# c12880ma-spectrometer-3_3v-breakout-mk-1.net
KiCad netlist of a schematic drawn in EAGLE
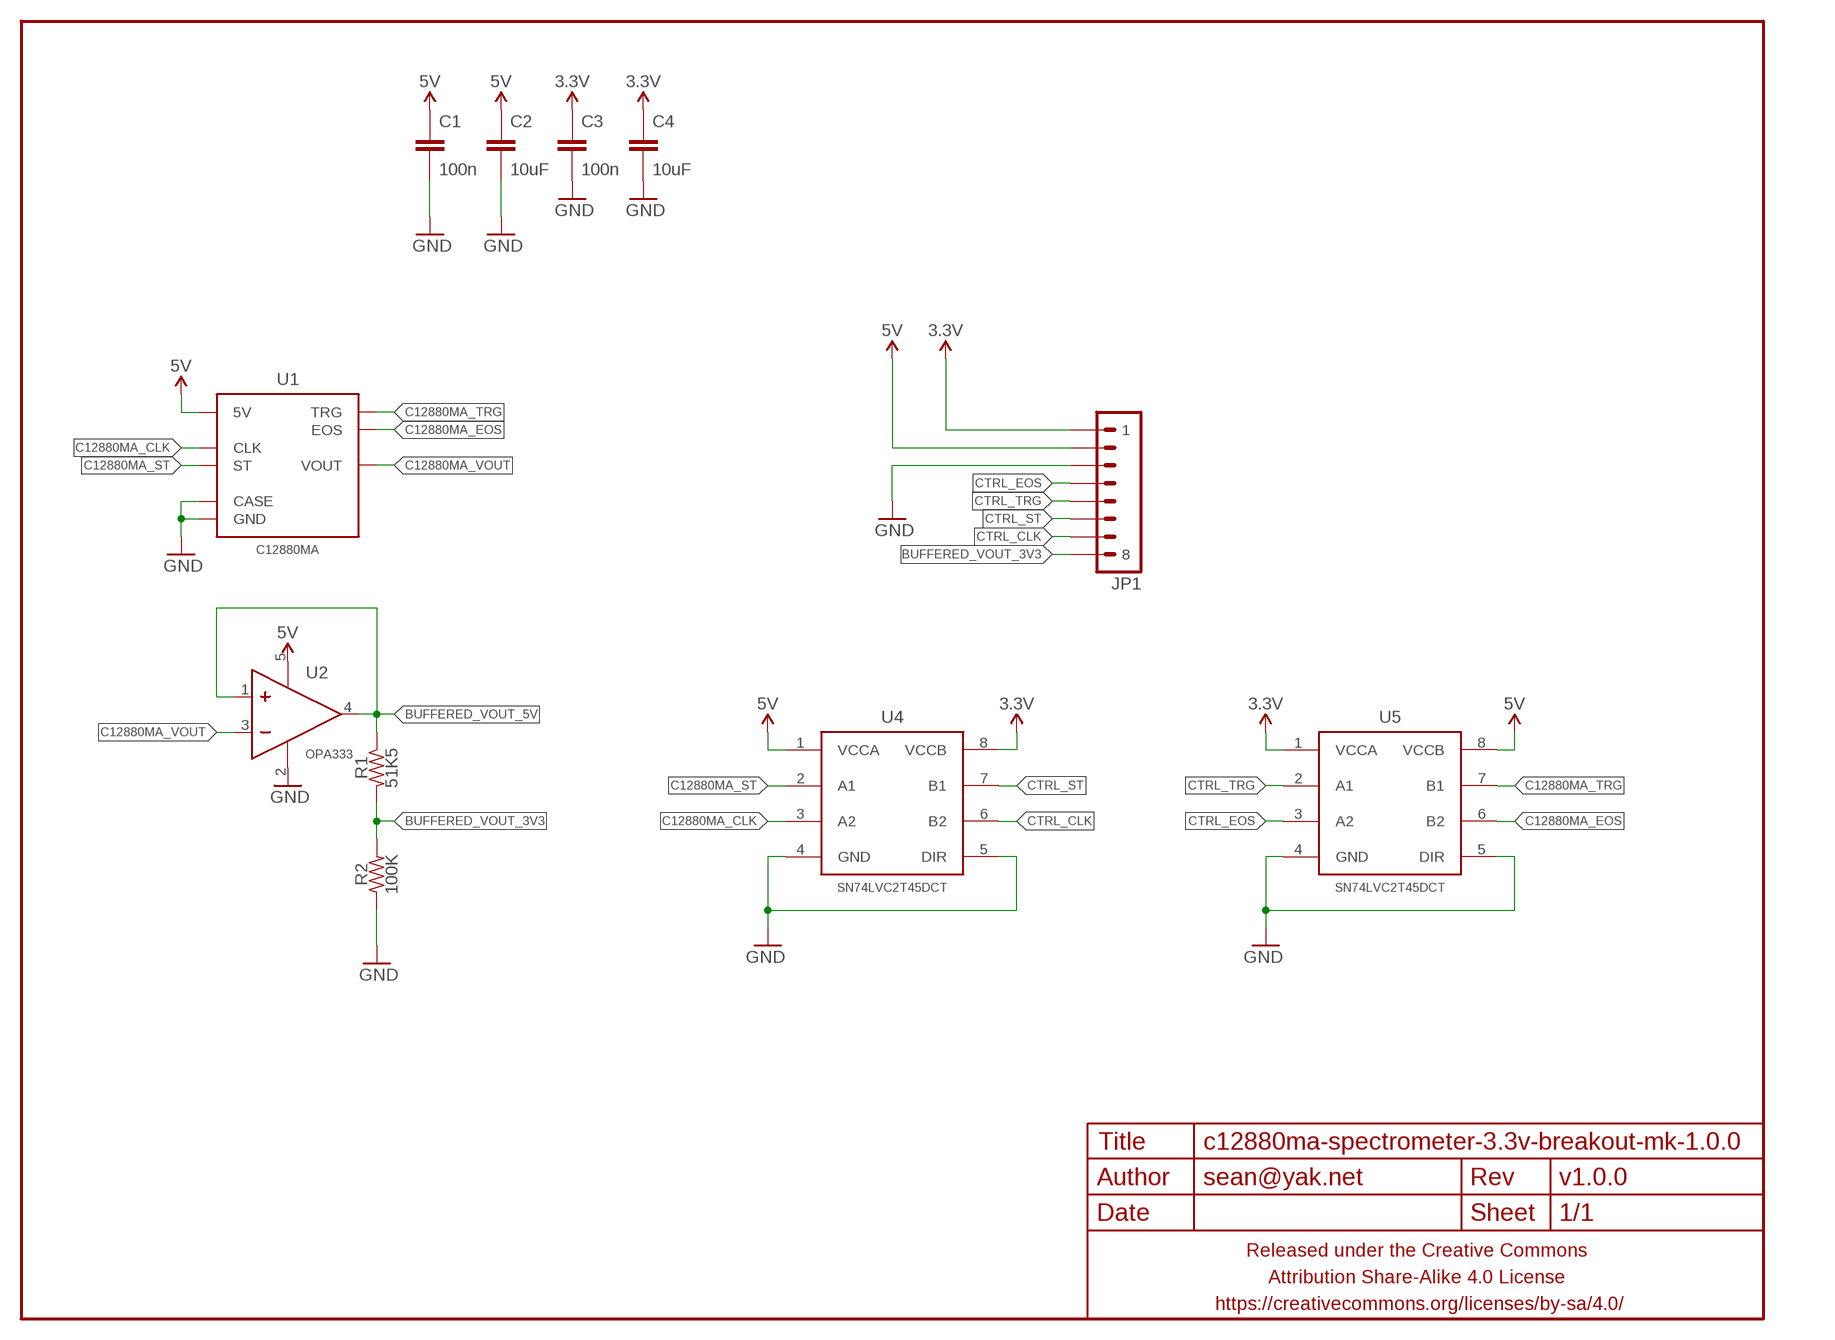
[diagram p0: schematic, sheet 1]

(export (version "E")
  (design (tool "Eeschema 10.0.6"))
  (components
    (comp (ref "C1")
      (value "100n")
      (footprint "eagle-import:C0402")
      (libsource (lib "eagle-import") (part "CAPACITOR-CERAMICC0402"))
    )
    (comp (ref "C2")
      (value "10uF")
      (footprint "eagle-import:C0603-TIGHTER")
      (libsource (lib "eagle-import") (part "CAPACITOR-CERAMICC0603-TIGHTER"))
    )
    (comp (ref "C3")
      (value "100n")
      (footprint "eagle-import:C0402")
      (libsource (lib "eagle-import") (part "CAPACITOR-CERAMICC0402"))
    )
    (comp (ref "C4")
      (value "10uF")
      (footprint "eagle-import:C0603-TIGHTER")
      (libsource (lib "eagle-import") (part "CAPACITOR-CERAMICC0603-TIGHTER"))
    )
    (comp (ref "FRAME1")
      (value "FRAME-LETTERNO_PACKAGE")
      (footprint "eagle-import:DUMMY")
      (fields
        (field (name "DESIGNER") "sean@yak.net")
        (field (name "VERSION") "v1.0.0")
        (field (name "DESIGNER_1") "sean@yak.net")
        (field (name "VERSION_1") "v1.0.0")
      )
      (libsource (lib "eagle-import") (part "FRAME-LETTERNO_PACKAGE"))
    )
    (comp (ref "JP1")
      (value "M081X08")
      (footprint "eagle-import:1X08")
      (libsource (lib "eagle-import") (part "M081X08"))
    )
    (comp (ref "R1")
      (value "51K5")
      (footprint "eagle-import:R0402")
      (libsource (lib "eagle-import") (part "RESISTORR0402"))
    )
    (comp (ref "R2")
      (value "100K")
      (footprint "eagle-import:R0402")
      (libsource (lib "eagle-import") (part "RESISTORR0402"))
    )
    (comp (ref "U1")
      (value "C12880MA")
      (footprint "eagle-import:DIL14")
      (libsource (lib "eagle-import") (part "C12880MA"))
    )
    (comp (ref "U2")
      (value "OPA333")
      (footprint "eagle-import:SC70")
      (libsource (lib "eagle-import") (part "OPAMPOPA333-SC-70"))
    )
    (comp (ref "U4")
      (value "SN74LVC2T45DCT")
      (footprint "eagle-import:SSOP-8")
      (libsource (lib "eagle-import") (part "SN74LVC2T45DCT"))
    )
    (comp (ref "U5")
      (value "SN74LVC2T45DCT")
      (footprint "eagle-import:SSOP-8")
      (libsource (lib "eagle-import") (part "SN74LVC2T45DCT"))
    )
  )
  (nets
    (net (code "1") (name "3.3V") (class "Default")
      (node (ref "C3") (pin "1") (pinfunction "1_1") (pintype "passive"))
      (node (ref "C4") (pin "1") (pinfunction "1_1") (pintype "passive"))
      (node (ref "JP1") (pin "1") (pinfunction "1_1") (pintype "passive"))
      (node (ref "U4") (pin "8") (pinfunction "VCCB_8") (pintype "bidirectional"))
      (node (ref "U5") (pin "1") (pinfunction "VCCA_1") (pintype "bidirectional"))
    )
    (net (code "2") (name "5V") (class "Default")
      (node (ref "C1") (pin "1") (pinfunction "1_1") (pintype "passive"))
      (node (ref "C2") (pin "1") (pinfunction "1_1") (pintype "passive"))
      (node (ref "JP1") (pin "2") (pinfunction "2_2") (pintype "passive"))
      (node (ref "U1") (pin "1") (pinfunction "5V_1") (pintype "bidirectional"))
      (node (ref "U1") (pin "5") (pinfunction "5V_5") (pintype "bidirectional"))
      (node (ref "U2") (pin "5") (pinfunction "V+_5") (pintype "power_in"))
      (node (ref "U4") (pin "1") (pinfunction "VCCA_1") (pintype "bidirectional"))
      (node (ref "U5") (pin "8") (pinfunction "VCCB_8") (pintype "bidirectional"))
    )
    (net (code "3") (name "BUFFERED_VOUT_3V3") (class "Default")
      (node (ref "JP1") (pin "8") (pinfunction "8_8") (pintype "passive"))
      (node (ref "R1") (pin "2") (pinfunction "2_2") (pintype "passive"))
      (node (ref "R2") (pin "2") (pinfunction "2_2") (pintype "passive"))
    )
    (net (code "4") (name "BUFFERED_VOUT_5V") (class "Default")
      (node (ref "R1") (pin "1") (pinfunction "1_1") (pintype "passive"))
      (node (ref "U2") (pin "1") (pinfunction "IN+_1") (pintype "input"))
      (node (ref "U2") (pin "4") (pinfunction "OUT_4") (pintype "output"))
    )
    (net (code "5") (name "C12880MA_CLK") (class "Default")
      (node (ref "U1") (pin "6") (pinfunction "CLK_6") (pintype "input"))
      (node (ref "U4") (pin "3") (pinfunction "A2_3") (pintype "bidirectional"))
    )
    (net (code "6") (name "C12880MA_EOS") (class "Default")
      (node (ref "U1") (pin "13") (pinfunction "EOS_13") (pintype "output"))
      (node (ref "U5") (pin "6") (pinfunction "B2_6") (pintype "bidirectional"))
    )
    (net (code "7") (name "C12880MA_ST") (class "Default")
      (node (ref "U1") (pin "8") (pinfunction "ST_8") (pintype "input"))
      (node (ref "U4") (pin "2") (pinfunction "A1_2") (pintype "bidirectional"))
    )
    (net (code "8") (name "C12880MA_TRG") (class "Default")
      (node (ref "U1") (pin "9") (pinfunction "TRG_9") (pintype "output"))
      (node (ref "U5") (pin "7") (pinfunction "B1_7") (pintype "bidirectional"))
    )
    (net (code "9") (name "C12880MA_VOUT") (class "Default")
      (node (ref "U1") (pin "14") (pinfunction "VOUT_14") (pintype "output"))
      (node (ref "U2") (pin "3") (pinfunction "IN-_3") (pintype "input"))
    )
    (net (code "10") (name "CTRL_CLK") (class "Default")
      (node (ref "JP1") (pin "7") (pinfunction "7_7") (pintype "passive"))
      (node (ref "U4") (pin "6") (pinfunction "B2_6") (pintype "bidirectional"))
    )
    (net (code "11") (name "CTRL_EOS") (class "Default")
      (node (ref "JP1") (pin "4") (pinfunction "4_4") (pintype "passive"))
      (node (ref "U5") (pin "3") (pinfunction "A2_3") (pintype "bidirectional"))
    )
    (net (code "12") (name "CTRL_ST") (class "Default")
      (node (ref "JP1") (pin "6") (pinfunction "6_6") (pintype "passive"))
      (node (ref "U4") (pin "7") (pinfunction "B1_7") (pintype "bidirectional"))
    )
    (net (code "13") (name "CTRL_TRG") (class "Default")
      (node (ref "JP1") (pin "5") (pinfunction "5_5") (pintype "passive"))
      (node (ref "U5") (pin "2") (pinfunction "A1_2") (pintype "bidirectional"))
    )
    (net (code "14") (name "GND") (class "Default")
      (node (ref "C1") (pin "2") (pinfunction "2_2") (pintype "passive"))
      (node (ref "C2") (pin "2") (pinfunction "2_2") (pintype "passive"))
      (node (ref "C3") (pin "2") (pinfunction "2_2") (pintype "passive"))
      (node (ref "C4") (pin "2") (pinfunction "2_2") (pintype "passive"))
      (node (ref "JP1") (pin "3") (pinfunction "3_3") (pintype "passive"))
      (node (ref "R2") (pin "1") (pinfunction "1_1") (pintype "passive"))
      (node (ref "U1") (pin "2") (pinfunction "GND_2") (pintype "bidirectional"))
      (node (ref "U1") (pin "7") (pinfunction "CASE_7") (pintype "bidirectional"))
      (node (ref "U2") (pin "2") (pinfunction "V-_2") (pintype "power_in"))
      (node (ref "U4") (pin "4") (pinfunction "GND_4") (pintype "bidirectional"))
      (node (ref "U4") (pin "5") (pinfunction "DIR_5") (pintype "bidirectional"))
      (node (ref "U5") (pin "4") (pinfunction "GND_4") (pintype "bidirectional"))
      (node (ref "U5") (pin "5") (pinfunction "DIR_5") (pintype "bidirectional"))
    )
  )
)
